# 2.net
KiCad netlist of a schematic drawn in EAGLE
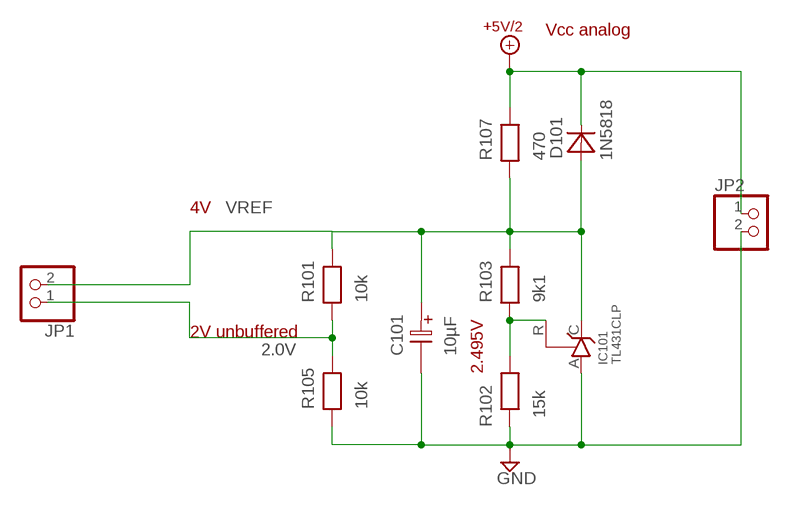
[diagram p0: schematic, sheet 1]

(export (version "E")
  (design (tool "Eeschema 10.0.6"))
  (components
    (comp (ref "C101")
      (value "10µF")
      (footprint "eagle-import:EL25B")
      (libsource (lib "eagle-import") (part "ELC-5"))
    )
    (comp (ref "D101")
      (value "1N5818")
      (footprint "eagle-import:D-10")
      (libsource (lib "eagle-import") (part "DIODE-10"))
    )
    (comp (ref "IC101")
      (value "TL431CLP")
      (footprint "eagle-import:TO92-CLP")
      (libsource (lib "eagle-import") (part "TL431CLP"))
    )
    (comp (ref "JP1")
      (value "PINHD-1X2")
      (footprint "eagle-import:1X02")
      (libsource (lib "eagle-import") (part "PINHD-1X2"))
    )
    (comp (ref "JP2")
      (value "PINHD-1X2")
      (footprint "eagle-import:1X02")
      (libsource (lib "eagle-import") (part "PINHD-1X2"))
    )
    (comp (ref "R101")
      (value "10k")
      (footprint "eagle-import:R-10")
      (libsource (lib "eagle-import") (part "RESEU-10"))
    )
    (comp (ref "R102")
      (value "15k")
      (footprint "eagle-import:R-10")
      (libsource (lib "eagle-import") (part "RESEU-10"))
    )
    (comp (ref "R103")
      (value "9k1")
      (footprint "eagle-import:R-10")
      (libsource (lib "eagle-import") (part "RESEU-10"))
    )
    (comp (ref "R105")
      (value "10k")
      (footprint "eagle-import:R-10")
      (libsource (lib "eagle-import") (part "RESEU-10"))
    )
    (comp (ref "R107")
      (value "470")
      (footprint "eagle-import:R-10")
      (libsource (lib "eagle-import") (part "RESEU-10"))
    )
  )
  (nets
    (net (code "1") (name "+5V{slash}2") (class "Default")
      (node (ref "D101") (pin "2") (pinfunction "K_2") (pintype "passive"))
      (node (ref "JP2") (pin "1") (pinfunction "1_1") (pintype "passive"))
      (node (ref "R107") (pin "2") (pinfunction "2_2") (pintype "passive"))
    )
    (net (code "2") (name "/2.0V") (class "Default")
      (node (ref "JP1") (pin "1") (pinfunction "1_1") (pintype "passive"))
      (node (ref "R101") (pin "1") (pinfunction "1_1") (pintype "passive"))
      (node (ref "R105") (pin "2") (pinfunction "2_2") (pintype "passive"))
    )
    (net (code "3") (name "/VREF") (class "Default")
      (node (ref "C101") (pin "1") (pinfunction "1_1") (pintype "passive"))
      (node (ref "D101") (pin "1") (pinfunction "A_1") (pintype "passive"))
      (node (ref "IC101") (pin "C") (pinfunction "C_C") (pintype "passive"))
      (node (ref "JP1") (pin "2") (pinfunction "2_2") (pintype "passive"))
      (node (ref "R101") (pin "2") (pinfunction "2_2") (pintype "passive"))
      (node (ref "R103") (pin "2") (pinfunction "2_2") (pintype "passive"))
      (node (ref "R107") (pin "1") (pinfunction "1_1") (pintype "passive"))
    )
    (net (code "4") (name "GND") (class "Default")
      (node (ref "C101") (pin "2") (pinfunction "2_2") (pintype "passive"))
      (node (ref "IC101") (pin "A") (pinfunction "A_A") (pintype "passive"))
      (node (ref "JP2") (pin "2") (pinfunction "2_2") (pintype "passive"))
      (node (ref "R102") (pin "1") (pinfunction "1_1") (pintype "passive"))
      (node (ref "R105") (pin "1") (pinfunction "1_1") (pintype "passive"))
    )
    (net (code "5") (name "Net-(IC101-PadR)") (class "Default")
      (node (ref "IC101") (pin "R") (pinfunction "R_R") (pintype "passive"))
      (node (ref "R102") (pin "2") (pinfunction "2_2") (pintype "passive"))
      (node (ref "R103") (pin "1") (pinfunction "1_1") (pintype "passive"))
    )
  )
)
